# medusa-AI.net
KiCad netlist of a schematic drawn in Altium Designer
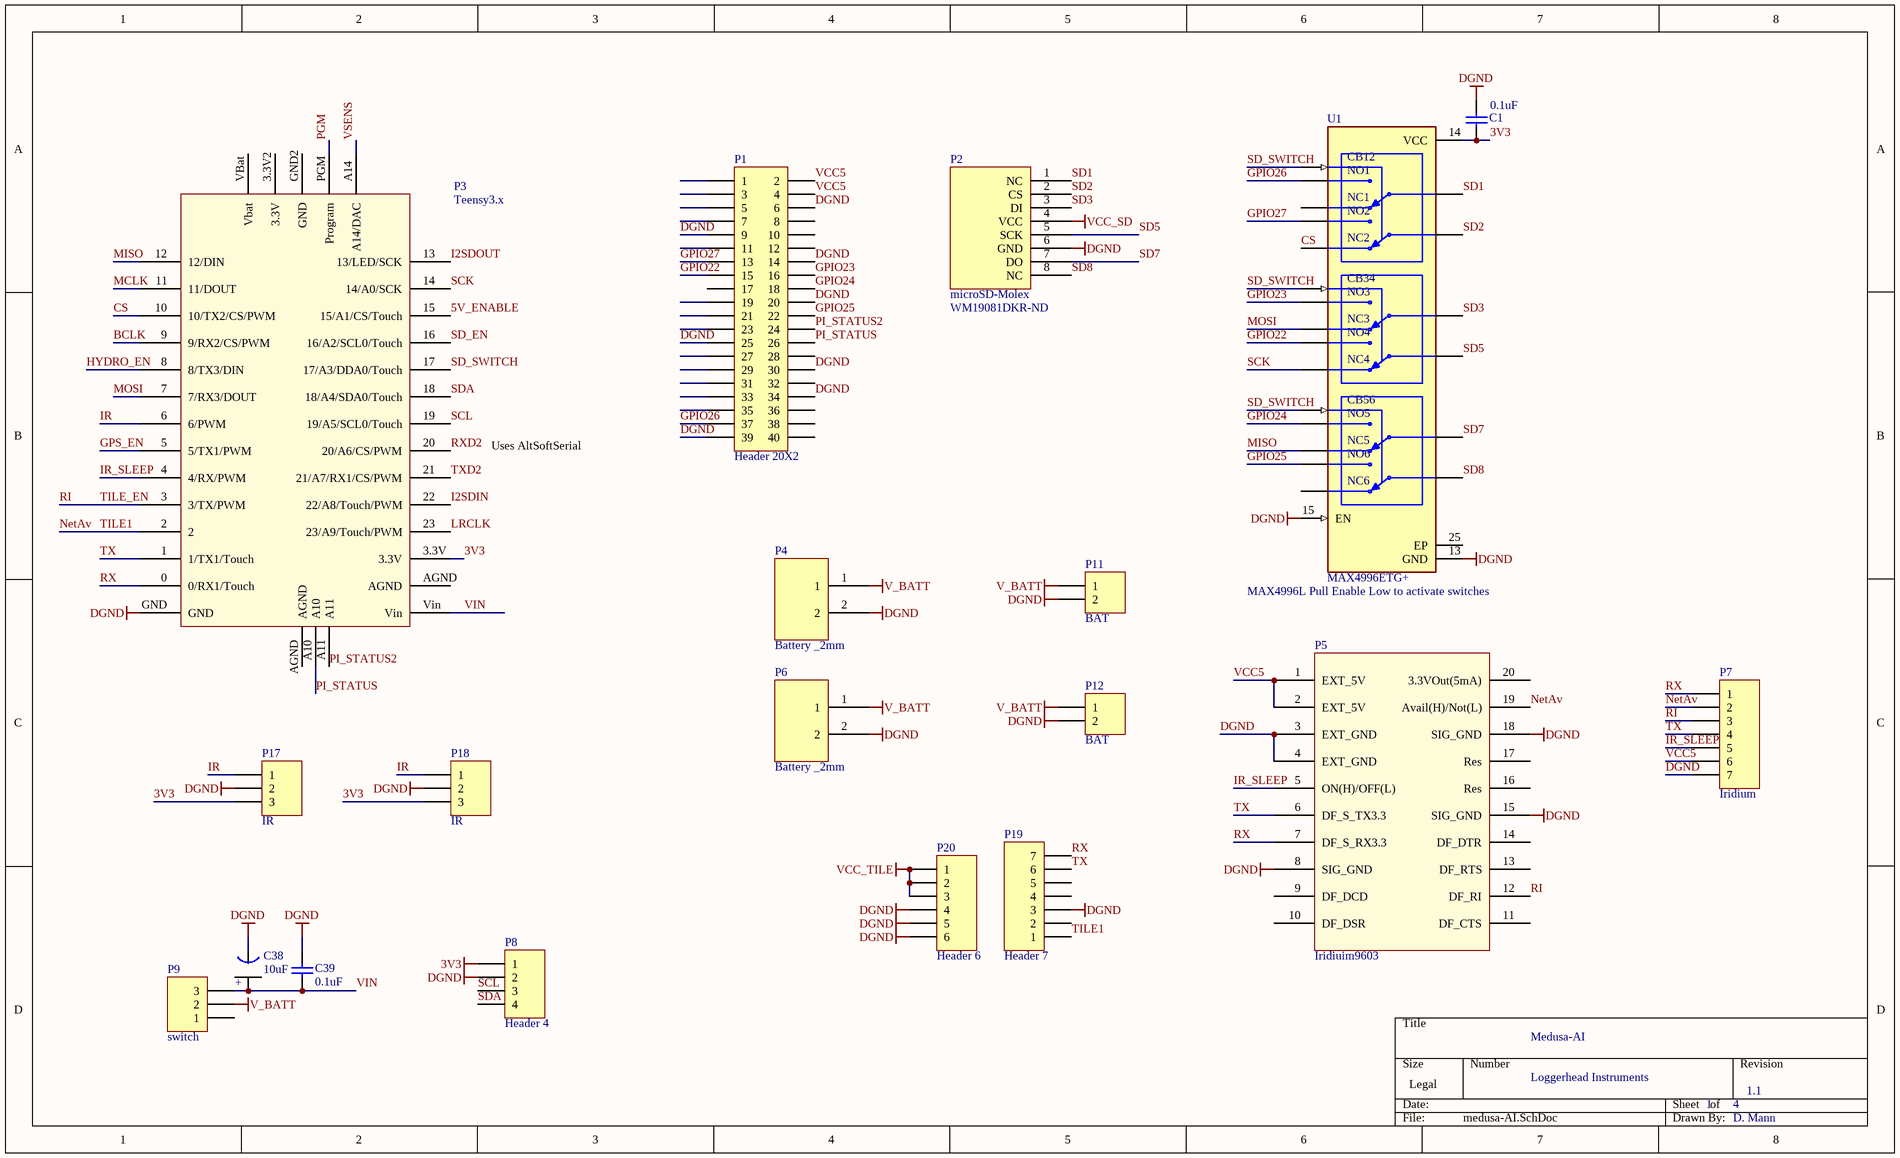
[diagram p0: medusa-AI.SchDoc]

(export (version "E")
  (design (tool "Eeschema 10.0.6"))
  (components
    (comp (ref "C1")
      (value "0.1uF")
      (footprint "0402")
      (description "Ceramic Chip Capacitor - Standard")
      (fields (field (name "PUBLISHER") "Altium Limited"))
      (libsource (lib "KEMET Chip Capacitor") (part "C0402"))
    )
    (comp (ref "C38") (value "10uF") (footprint "Tant0805") (libsource (lib "Loggerhead") (part "Tant0805")))
    (comp (ref "C39")
      (value "0.1uF")
      (footprint "0402")
      (description "Ceramic Chip Capacitor - Standard")
      (fields (field (name "PUBLISHER") "Altium Limited"))
      (libsource (lib "KEMET Chip Capacitor") (part "C0402"))
    )
    (comp (ref "P1")
      (value "Header 20X2")
      (footprint "HDR2X20")
      (description "Header, 20-Pin, Dual row")
      (fields (field (name "PUBLISHER") "Altium Limited"))
      (libsource (lib "Miscellaneous Connectors") (part "Header 20X2"))
    )
    (comp (ref "P2")
      (value "microSD-Molex")
      (footprint "microSD_Molex_hinged")
      (fields (field (name "SUPPLIER PART NUMBER 1") "WM19081DKR-ND"))
      (libsource (lib "Loggerhead") (part "microSD_Molex_hinged"))
    )
    (comp (ref "P3")
      (value "Teensy3.x")
      (footprint "Teensy3.x")
      (libsource (lib "Teensy") (part "Teensy3.x"))
    )
    (comp (ref "P4")
      (value "Battery _2mm")
      (footprint "HDR_2x1_2mm")
      (description "Charging Connector")
      (libsource (lib "Loggerhead") (part "HDR_2x1_2mm"))
    )
    (comp (ref "P5")
      (value "Iridiuim9603")
      (footprint "Iridium9603")
      (libsource (lib "Loggerhead") (part "IRIDIUM9603"))
    )
    (comp (ref "P6")
      (value "Battery _2mm")
      (footprint "HDR_2x1_2mm")
      (description "Charging Connector")
      (libsource (lib "Loggerhead") (part "HDR_2x1_2mm"))
    )
    (comp (ref "P7")
      (value "Iridium")
      (footprint "HDR1X7")
      (description "Header, 7-Pin")
      (fields (field (name "PUBLISHER") "Altium Limited"))
      (libsource (lib "Miscellaneous Connectors") (part "Header 7"))
    )
    (comp (ref "P8")
      (value "Header 4")
      (footprint "HDR1X4")
      (description "Header, 4-Pin")
      (fields (field (name "PUBLISHER") "Altium Limited"))
      (libsource (lib "Miscellaneous Connectors") (part "Header 4"))
    )
    (comp (ref "P9")
      (value "switch")
      (footprint "HDR1X3")
      (description "Header, 3-Pin")
      (fields (field (name "PUBLISHER") "Altium Limited"))
      (libsource (lib "") (part "Header 3_1"))
    )
    (comp (ref "P11")
      (value "BAT")
      (footprint "HDR1X2")
      (description "Header, 2-Pin")
      (fields (field (name "PUBLISHER") "Altium Limited"))
      (libsource (lib "Miscellaneous Connectors") (part "Header 2"))
    )
    (comp (ref "P12")
      (value "BAT")
      (footprint "HDR1X2")
      (description "Header, 2-Pin")
      (fields (field (name "PUBLISHER") "Altium Limited"))
      (libsource (lib "Miscellaneous Connectors") (part "Header 2"))
    )
    (comp (ref "P17")
      (value "IR")
      (footprint "HDR1X3")
      (description "Header, 3-Pin")
      (fields (field (name "PUBLISHER") "Altium Limited"))
      (libsource (lib "Miscellaneous Connectors") (part "Header 3"))
    )
    (comp (ref "P18")
      (value "IR")
      (footprint "HDR1X3")
      (description "Header, 3-Pin")
      (fields (field (name "PUBLISHER") "Altium Limited"))
      (libsource (lib "Miscellaneous Connectors") (part "Header 3"))
    )
    (comp (ref "P19")
      (value "Header 7")
      (footprint "HDR1X7")
      (description "Header, 7-Pin")
      (fields (field (name "PUBLISHER") "Altium Limited"))
      (libsource (lib "") (part "Header 7_1"))
    )
    (comp (ref "P20")
      (value "Header 6")
      (footprint "HDR1X6")
      (description "Header, 6-Pin")
      (fields (field (name "PUBLISHER") "Altium Limited"))
      (libsource (lib "Miscellaneous Connectors") (part "Header 6"))
    )
    (comp (ref "U1")
      (value "MAX4996ETG+")
      (footprint "QFN40P350X350X80-25N")
      (description "3 Circuit IC Switch 2:2 4Ohm 24-TQFN (4x4)")
      (fields (field (name "MF") "Maxim Integrated"))
      (libsource (lib "MAX4996ETG_") (part "MAX4996ETG+"))
    )
  )
  (nets
    (net (code "1") (name "/5V_ENABLE") (class "Default")
      (node (ref "P3") (pin "15") (pinfunction "15/A1/CS/Touch_15") (pintype "passive"))
    )
    (net (code "2") (name "/BCLK") (class "Default")
      (node (ref "P3") (pin "9") (pinfunction "9/RX2/CS/PWM_9") (pintype "passive"))
    )
    (net (code "3") (name "/CS") (class "Default")
      (node (ref "P3") (pin "10") (pinfunction "10/TX2/CS/PWM_10") (pintype "passive"))
      (node (ref "U1") (pin "11") (pinfunction "NC2_11") (pintype "passive"))
    )
    (net (code "4") (name "/GPIO22") (class "Default")
      (node (ref "P1") (pin "15") (pinfunction "15_15") (pintype "passive"))
      (node (ref "U1") (pin "22") (pinfunction "NO4_22") (pintype "passive"))
    )
    (net (code "5") (name "/GPIO23") (class "Default")
      (node (ref "P1") (pin "16") (pinfunction "16_16") (pintype "passive"))
      (node (ref "U1") (pin "21") (pinfunction "NO3_21") (pintype "passive"))
    )
    (net (code "6") (name "/GPIO24") (class "Default")
      (node (ref "P1") (pin "18") (pinfunction "18_18") (pintype "passive"))
      (node (ref "U1") (pin "23") (pinfunction "NO5_23") (pintype "passive"))
    )
    (net (code "7") (name "/GPIO25") (class "Default")
      (node (ref "P1") (pin "22") (pinfunction "22_22") (pintype "passive"))
      (node (ref "U1") (pin "24") (pinfunction "NO6_24") (pintype "passive"))
    )
    (net (code "8") (name "/GPIO26") (class "Default")
      (node (ref "P1") (pin "37") (pinfunction "37_37") (pintype "passive"))
      (node (ref "U1") (pin "19") (pinfunction "NO1_19") (pintype "passive"))
    )
    (net (code "9") (name "/GPIO27") (class "Default")
      (node (ref "P1") (pin "13") (pinfunction "13_13") (pintype "passive"))
      (node (ref "U1") (pin "20") (pinfunction "NO2_20") (pintype "passive"))
    )
    (net (code "10") (name "/GPS_EN") (class "Default")
      (node (ref "P3") (pin "5") (pinfunction "5/TX1/PWM_5") (pintype "passive"))
    )
    (net (code "11") (name "/HYDRO_EN") (class "Default")
      (node (ref "P3") (pin "8") (pinfunction "8/TX3/DIN_8") (pintype "passive"))
    )
    (net (code "12") (name "/I2SDIN") (class "Default")
      (node (ref "P3") (pin "22") (pinfunction "22/A8/Touch/PWM_22") (pintype "passive"))
    )
    (net (code "13") (name "/I2SDOUT") (class "Default")
      (node (ref "P3") (pin "13") (pinfunction "13/LED/SCK_13") (pintype "passive"))
    )
    (net (code "14") (name "/IR") (class "Default")
      (node (ref "P17") (pin "1") (pinfunction "1_1") (pintype "passive"))
      (node (ref "P18") (pin "1") (pinfunction "1_1") (pintype "passive"))
      (node (ref "P3") (pin "6") (pinfunction "6/PWM_6") (pintype "passive"))
    )
    (net (code "15") (name "/IR_SLEEP") (class "Default")
      (node (ref "P3") (pin "4") (pinfunction "4/RX/PWM_4") (pintype "passive"))
      (node (ref "P5") (pin "5") (pinfunction "ON(H)/OFF(L)_5") (pintype "passive"))
      (node (ref "P7") (pin "5") (pinfunction "5_5") (pintype "passive"))
    )
    (net (code "16") (name "/LRCLK") (class "Default")
      (node (ref "P3") (pin "23") (pinfunction "23/A9/Touch/PWM_23") (pintype "passive"))
    )
    (net (code "17") (name "/MCLK") (class "Default")
      (node (ref "P3") (pin "11") (pinfunction "11/DOUT_11") (pintype "passive"))
    )
    (net (code "18") (name "/MISO") (class "Default")
      (node (ref "P3") (pin "12") (pinfunction "12/DIN_12") (pintype "passive"))
      (node (ref "U1") (pin "8") (pinfunction "NC5_8") (pintype "passive"))
    )
    (net (code "19") (name "/MOSI") (class "Default")
      (node (ref "P3") (pin "7") (pinfunction "7/RX3/DOUT_7") (pintype "passive"))
      (node (ref "U1") (pin "10") (pinfunction "NC3_10") (pintype "passive"))
    )
    (net (code "20") (name "/NetAv") (class "Default")
      (node (ref "P19") (pin "1") (pinfunction "1_1") (pintype "passive"))
      (node (ref "P3") (pin "2") (pinfunction "2_2") (pintype "passive"))
      (node (ref "P5") (pin "19") (pinfunction "Avail(H)/Not(L)_19") (pintype "passive"))
      (node (ref "P7") (pin "2") (pinfunction "2_2") (pintype "passive"))
    )
    (net (code "21") (name "/PGM") (class "Default")
      (node (ref "P3") (pin "PGM") (pinfunction "Program_PGM") (pintype "passive"))
    )
    (net (code "22") (name "/PI_STATUS") (class "Default")
      (node (ref "P1") (pin "26") (pinfunction "26_26") (pintype "passive"))
      (node (ref "P3") (pin "A10") (pinfunction "A10_A10") (pintype "passive"))
    )
    (net (code "23") (name "/PI_STATUS2") (class "Default")
      (node (ref "P1") (pin "24") (pinfunction "24_24") (pintype "passive"))
      (node (ref "P3") (pin "A11") (pinfunction "A11_A11") (pintype "passive"))
    )
    (net (code "24") (name "/RI") (class "Default")
      (node (ref "P3") (pin "3") (pinfunction "3/TX/PWM_3") (pintype "passive"))
      (node (ref "P5") (pin "12") (pinfunction "DF_RI_12") (pintype "passive"))
      (node (ref "P7") (pin "3") (pinfunction "3_3") (pintype "passive"))
    )
    (net (code "25") (name "/RX") (class "Default")
      (node (ref "P19") (pin "7") (pinfunction "7_7") (pintype "passive"))
      (node (ref "P3") (pin "0") (pinfunction "0/RX1/Touch_0") (pintype "passive"))
      (node (ref "P5") (pin "7") (pinfunction "DF_S_RX3.3_7") (pintype "passive"))
      (node (ref "P7") (pin "1") (pinfunction "1_1") (pintype "passive"))
    )
    (net (code "26") (name "/RXD2") (class "Default")
      (node (ref "P3") (pin "20") (pinfunction "20/A6/CS/PWM_20") (pintype "passive"))
    )
    (net (code "27") (name "/SCK") (class "Default")
      (node (ref "P3") (pin "14") (pinfunction "14/A0/SCK_14") (pintype "passive"))
      (node (ref "U1") (pin "9") (pinfunction "NC4_9") (pintype "passive"))
    )
    (net (code "28") (name "/SCL") (class "Default")
      (node (ref "P3") (pin "19") (pinfunction "19/A5/SCL0/Touch_19") (pintype "passive"))
      (node (ref "P8") (pin "3") (pinfunction "3_3") (pintype "passive"))
    )
    (net (code "29") (name "/SD1") (class "Default")
      (node (ref "P2") (pin "1") (pinfunction "NC_1") (pintype "passive"))
      (node (ref "U1") (pin "18") (pinfunction "COM1_18") (pintype "passive"))
    )
    (net (code "30") (name "/SD2") (class "Default")
      (node (ref "P2") (pin "2") (pinfunction "CS_2") (pintype "passive"))
      (node (ref "U1") (pin "17") (pinfunction "COM2_17") (pintype "passive"))
    )
    (net (code "31") (name "/SD3") (class "Default")
      (node (ref "P2") (pin "3") (pinfunction "DI_3") (pintype "passive"))
      (node (ref "U1") (pin "16") (pinfunction "COM3_16") (pintype "passive"))
    )
    (net (code "32") (name "/SD5") (class "Default")
      (node (ref "P2") (pin "5") (pinfunction "SCK_5") (pintype "passive"))
      (node (ref "U1") (pin "4") (pinfunction "COM4_4") (pintype "passive"))
    )
    (net (code "33") (name "/SD7") (class "Default")
      (node (ref "P2") (pin "7") (pinfunction "DO_7") (pintype "passive"))
      (node (ref "U1") (pin "5") (pinfunction "COM5_5") (pintype "passive"))
    )
    (net (code "34") (name "/SD8") (class "Default")
      (node (ref "P2") (pin "8") (pinfunction "NC_8") (pintype "passive"))
      (node (ref "U1") (pin "6") (pinfunction "COM6_6") (pintype "passive"))
    )
    (net (code "35") (name "/SDA") (class "Default")
      (node (ref "P3") (pin "18") (pinfunction "18/A4/SDA0/Touch_18") (pintype "passive"))
      (node (ref "P8") (pin "4") (pinfunction "4_4") (pintype "passive"))
    )
    (net (code "36") (name "/SD_EN") (class "Default")
      (node (ref "P3") (pin "16") (pinfunction "16/A2/SCL0/Touch_16") (pintype "passive"))
    )
    (net (code "37") (name "/SD_SWITCH") (class "Default")
      (node (ref "P3") (pin "17") (pinfunction "17/A3/DDA0/Touch_17") (pintype "passive"))
      (node (ref "U1") (pin "1") (pinfunction "CB12_1") (pintype "input"))
      (node (ref "U1") (pin "2") (pinfunction "CB34_2") (pintype "input"))
      (node (ref "U1") (pin "3") (pinfunction "CB56_3") (pintype "input"))
    )
    (net (code "38") (name "/TX") (class "Default")
      (node (ref "P19") (pin "6") (pinfunction "6_6") (pintype "passive"))
      (node (ref "P3") (pin "1") (pinfunction "1/TX1/Touch_1") (pintype "passive"))
      (node (ref "P5") (pin "6") (pinfunction "DF_S_TX3.3_6") (pintype "passive"))
      (node (ref "P7") (pin "4") (pinfunction "4_4") (pintype "passive"))
    )
    (net (code "39") (name "/TXD2") (class "Default")
      (node (ref "P3") (pin "21") (pinfunction "21/A7/RX1/CS/PWM_21") (pintype "passive"))
    )
    (net (code "40") (name "/VCC5") (class "Default")
      (node (ref "P1") (pin "2") (pinfunction "2_2") (pintype "passive"))
      (node (ref "P1") (pin "4") (pinfunction "4_4") (pintype "passive"))
      (node (ref "P5") (pin "1") (pinfunction "EXT_5V_1") (pintype "passive"))
      (node (ref "P5") (pin "2") (pinfunction "EXT_5V_2") (pintype "passive"))
      (node (ref "P7") (pin "6") (pinfunction "6_6") (pintype "passive"))
    )
    (net (code "41") (name "/VIN") (class "Default")
      (node (ref "C38") (pin "2") (pinfunction "+_2") (pintype "passive"))
      (node (ref "C39") (pin "1") (pinfunction "1_1") (pintype "passive"))
      (node (ref "P3") (pin "Vin") (pinfunction "Vin_Vin") (pintype "passive"))
      (node (ref "P9") (pin "3") (pinfunction "3_3") (pintype "passive"))
    )
    (net (code "42") (name "/VSENS") (class "Default")
      (node (ref "P3") (pin "A14") (pinfunction "A14/DAC_A14") (pintype "passive"))
    )
    (net (code "43") (name "3V3") (class "Default")
      (node (ref "C1") (pin "1") (pinfunction "1_1") (pintype "passive"))
      (node (ref "P17") (pin "3") (pinfunction "3_3") (pintype "passive"))
      (node (ref "P18") (pin "3") (pinfunction "3_3") (pintype "passive"))
      (node (ref "P3") (pin "3.3V") (pinfunction "3.3V_3.3V") (pintype "passive"))
      (node (ref "P8") (pin "1") (pinfunction "1_1") (pintype "passive"))
      (node (ref "U1") (pin "14") (pinfunction "VCC_14") (pintype "power_in"))
    )
    (net (code "44") (name "DGND") (class "Default")
      (node (ref "C1") (pin "2") (pinfunction "2_2") (pintype "passive"))
      (node (ref "C38") (pin "1") (pinfunction "GND_1") (pintype "passive"))
      (node (ref "C39") (pin "2") (pinfunction "2_2") (pintype "passive"))
      (node (ref "P1") (pin "14") (pinfunction "14_14") (pintype "passive"))
      (node (ref "P1") (pin "20") (pinfunction "20_20") (pintype "passive"))
      (node (ref "P1") (pin "25") (pinfunction "25_25") (pintype "passive"))
      (node (ref "P1") (pin "30") (pinfunction "30_30") (pintype "passive"))
      (node (ref "P1") (pin "34") (pinfunction "34_34") (pintype "passive"))
      (node (ref "P1") (pin "39") (pinfunction "39_39") (pintype "passive"))
      (node (ref "P1") (pin "6") (pinfunction "6_6") (pintype "passive"))
      (node (ref "P1") (pin "9") (pinfunction "9_9") (pintype "passive"))
      (node (ref "P11") (pin "2") (pinfunction "2_2") (pintype "passive"))
      (node (ref "P12") (pin "2") (pinfunction "2_2") (pintype "passive"))
      (node (ref "P17") (pin "2") (pinfunction "2_2") (pintype "passive"))
      (node (ref "P18") (pin "2") (pinfunction "2_2") (pintype "passive"))
      (node (ref "P19") (pin "3") (pinfunction "3_3") (pintype "passive"))
      (node (ref "P2") (pin "6") (pinfunction "GND_6") (pintype "passive"))
      (node (ref "P20") (pin "4") (pinfunction "4_4") (pintype "passive"))
      (node (ref "P20") (pin "5") (pinfunction "5_5") (pintype "passive"))
      (node (ref "P20") (pin "6") (pinfunction "6_6") (pintype "passive"))
      (node (ref "P3") (pin "GND") (pinfunction "GND_GND") (pintype "passive"))
      (node (ref "P4") (pin "2") (pinfunction "2_2") (pintype "passive"))
      (node (ref "P5") (pin "15") (pinfunction "SIG_GND_15") (pintype "passive"))
      (node (ref "P5") (pin "18") (pinfunction "SIG_GND_18") (pintype "passive"))
      (node (ref "P5") (pin "3") (pinfunction "EXT_GND_3") (pintype "passive"))
      (node (ref "P5") (pin "4") (pinfunction "EXT_GND_4") (pintype "passive"))
      (node (ref "P5") (pin "8") (pinfunction "SIG_GND_8") (pintype "passive"))
      (node (ref "P6") (pin "2") (pinfunction "2_2") (pintype "passive"))
      (node (ref "P7") (pin "7") (pinfunction "7_7") (pintype "passive"))
      (node (ref "P8") (pin "2") (pinfunction "2_2") (pintype "passive"))
      (node (ref "U1") (pin "13") (pinfunction "GND_13") (pintype "power_in"))
      (node (ref "U1") (pin "15") (pinfunction "EN_15") (pintype "input"))
    )
    (net (code "45") (name "VCC_SD") (class "Default")
      (node (ref "P2") (pin "4") (pinfunction "VCC_4") (pintype "passive"))
    )
    (net (code "46") (name "VCC_TILE") (class "Default")
      (node (ref "P20") (pin "1") (pinfunction "1_1") (pintype "passive"))
      (node (ref "P20") (pin "2") (pinfunction "2_2") (pintype "passive"))
      (node (ref "P20") (pin "3") (pinfunction "3_3") (pintype "passive"))
    )
    (net (code "47") (name "V_BATT") (class "Default")
      (node (ref "P11") (pin "1") (pinfunction "1_1") (pintype "passive"))
      (node (ref "P12") (pin "1") (pinfunction "1_1") (pintype "passive"))
      (node (ref "P4") (pin "1") (pinfunction "1_1") (pintype "passive"))
      (node (ref "P6") (pin "1") (pinfunction "1_1") (pintype "passive"))
      (node (ref "P9") (pin "2") (pinfunction "2_2") (pintype "passive"))
    )
    (net (code "48") (name "unconnected-(P1-Pad1)") (class "Default")
      (node (ref "P1") (pin "1") (pinfunction "1_1") (pintype "passive"))
    )
    (net (code "49") (name "unconnected-(P1-Pad3)") (class "Default")
      (node (ref "P1") (pin "3") (pinfunction "3_3") (pintype "passive"))
    )
    (net (code "50") (name "unconnected-(P1-Pad5)") (class "Default")
      (node (ref "P1") (pin "5") (pinfunction "5_5") (pintype "passive"))
    )
    (net (code "51") (name "unconnected-(P1-Pad7)") (class "Default")
      (node (ref "P1") (pin "7") (pinfunction "7_7") (pintype "passive"))
    )
    (net (code "52") (name "unconnected-(P1-Pad8)") (class "Default")
      (node (ref "P1") (pin "8") (pinfunction "8_8") (pintype "passive"))
    )
    (net (code "53") (name "unconnected-(P1-Pad10)") (class "Default")
      (node (ref "P1") (pin "10") (pinfunction "10_10") (pintype "passive"))
    )
    (net (code "54") (name "unconnected-(P1-Pad11)") (class "Default")
      (node (ref "P1") (pin "11") (pinfunction "11_11") (pintype "passive"))
    )
    (net (code "55") (name "unconnected-(P1-Pad12)") (class "Default")
      (node (ref "P1") (pin "12") (pinfunction "12_12") (pintype "passive"))
    )
    (net (code "56") (name "unconnected-(P1-Pad17)") (class "Default")
      (node (ref "P1") (pin "17") (pinfunction "17_17") (pintype "passive"))
    )
    (net (code "57") (name "unconnected-(P1-Pad19)") (class "Default")
      (node (ref "P1") (pin "19") (pinfunction "19_19") (pintype "passive"))
    )
    (net (code "58") (name "unconnected-(P1-Pad21)") (class "Default")
      (node (ref "P1") (pin "21") (pinfunction "21_21") (pintype "passive"))
    )
    (net (code "59") (name "unconnected-(P1-Pad23)") (class "Default")
      (node (ref "P1") (pin "23") (pinfunction "23_23") (pintype "passive"))
    )
    (net (code "60") (name "unconnected-(P1-Pad27)") (class "Default")
      (node (ref "P1") (pin "27") (pinfunction "27_27") (pintype "passive"))
    )
    (net (code "61") (name "unconnected-(P1-Pad28)") (class "Default")
      (node (ref "P1") (pin "28") (pinfunction "28_28") (pintype "passive"))
    )
    (net (code "62") (name "unconnected-(P1-Pad29)") (class "Default")
      (node (ref "P1") (pin "29") (pinfunction "29_29") (pintype "passive"))
    )
    (net (code "63") (name "unconnected-(P1-Pad31)") (class "Default")
      (node (ref "P1") (pin "31") (pinfunction "31_31") (pintype "passive"))
    )
    (net (code "64") (name "unconnected-(P1-Pad32)") (class "Default")
      (node (ref "P1") (pin "32") (pinfunction "32_32") (pintype "passive"))
    )
    (net (code "65") (name "unconnected-(P1-Pad33)") (class "Default")
      (node (ref "P1") (pin "33") (pinfunction "33_33") (pintype "passive"))
    )
    (net (code "66") (name "unconnected-(P1-Pad35)") (class "Default")
      (node (ref "P1") (pin "35") (pinfunction "35_35") (pintype "passive"))
    )
    (net (code "67") (name "unconnected-(P1-Pad36)") (class "Default")
      (node (ref "P1") (pin "36") (pinfunction "36_36") (pintype "passive"))
    )
    (net (code "68") (name "unconnected-(P1-Pad38)") (class "Default")
      (node (ref "P1") (pin "38") (pinfunction "38_38") (pintype "passive"))
    )
    (net (code "69") (name "unconnected-(P1-Pad40)") (class "Default")
      (node (ref "P1") (pin "40") (pinfunction "40_40") (pintype "passive"))
    )
    (net (code "70") (name "unconnected-(P3-3.3V-Pad3.3V2)") (class "Default")
      (node (ref "P3") (pin "3.3V2") (pinfunction "3.3V_3.3V2") (pintype "passive"))
    )
    (net (code "71") (name "unconnected-(P3-GND-PadGND2)") (class "Default")
      (node (ref "P3") (pin "GND2") (pinfunction "GND_GND2") (pintype "passive"))
    )
    (net (code "72") (name "unconnected-(P3-PadAGND)") (class "Default")
      (node (ref "P3") (pin "AGND") (pinfunction "AGND_AGND") (pintype "passive"))
    )
    (net (code "73") (name "unconnected-(P3-PadAGND)_1") (class "Default")
      (node (ref "P3") (pin "AGND") (pinfunction "AGND_AGND") (pintype "passive"))
    )
    (net (code "74") (name "unconnected-(P3-Vbat-PadVBat)") (class "Default")
      (node (ref "P3") (pin "VBat") (pinfunction "Vbat_VBat") (pintype "passive"))
    )
    (net (code "75") (name "unconnected-(P5-3.3VOut(5mA)-Pad20)") (class "Default")
      (node (ref "P5") (pin "20") (pinfunction "3.3VOut(5mA)_20") (pintype "passive"))
    )
    (net (code "76") (name "unconnected-(P5-DF_CTS-Pad11)") (class "Default")
      (node (ref "P5") (pin "11") (pinfunction "DF_CTS_11") (pintype "passive"))
    )
    (net (code "77") (name "unconnected-(P5-DF_DCD-Pad9)") (class "Default")
      (node (ref "P5") (pin "9") (pinfunction "DF_DCD_9") (pintype "passive"))
    )
    (net (code "78") (name "unconnected-(P5-DF_DSR-Pad10)") (class "Default")
      (node (ref "P5") (pin "10") (pinfunction "DF_DSR_10") (pintype "passive"))
    )
    (net (code "79") (name "unconnected-(P5-DF_DTR-Pad14)") (class "Default")
      (node (ref "P5") (pin "14") (pinfunction "DF_DTR_14") (pintype "passive"))
    )
    (net (code "80") (name "unconnected-(P5-DF_RTS-Pad13)") (class "Default")
      (node (ref "P5") (pin "13") (pinfunction "DF_RTS_13") (pintype "passive"))
    )
    (net (code "81") (name "unconnected-(P5-Res-Pad16)") (class "Default")
      (node (ref "P5") (pin "16") (pinfunction "Res_16") (pintype "passive"))
    )
    (net (code "82") (name "unconnected-(P5-Res-Pad17)") (class "Default")
      (node (ref "P5") (pin "17") (pinfunction "Res_17") (pintype "passive"))
    )
    (net (code "83") (name "unconnected-(P9-Pad1)") (class "Default")
      (node (ref "P9") (pin "1") (pinfunction "1_1") (pintype "passive"))
    )
    (net (code "84") (name "unconnected-(P19-Pad2)") (class "Default")
      (node (ref "P19") (pin "2") (pinfunction "2_2") (pintype "passive"))
    )
    (net (code "85") (name "unconnected-(P19-Pad4)") (class "Default")
      (node (ref "P19") (pin "4") (pinfunction "4_4") (pintype "passive"))
    )
    (net (code "86") (name "unconnected-(P19-Pad5)") (class "Default")
      (node (ref "P19") (pin "5") (pinfunction "5_5") (pintype "passive"))
    )
    (net (code "87") (name "unconnected-(U1-EP-Pad25)") (class "Default")
      (node (ref "U1") (pin "25") (pinfunction "EP_25") (pintype "power_in"))
    )
    (net (code "88") (name "unconnected-(U1-NC1-Pad12)") (class "Default")
      (node (ref "U1") (pin "12") (pinfunction "NC1_12") (pintype "passive"))
    )
    (net (code "89") (name "unconnected-(U1-NC6-Pad7)") (class "Default")
      (node (ref "U1") (pin "7") (pinfunction "NC6_7") (pintype "passive"))
    )
  )
)
